# IPMC_Control.net
KiCad netlist of a schematic drawn in Altium Designer
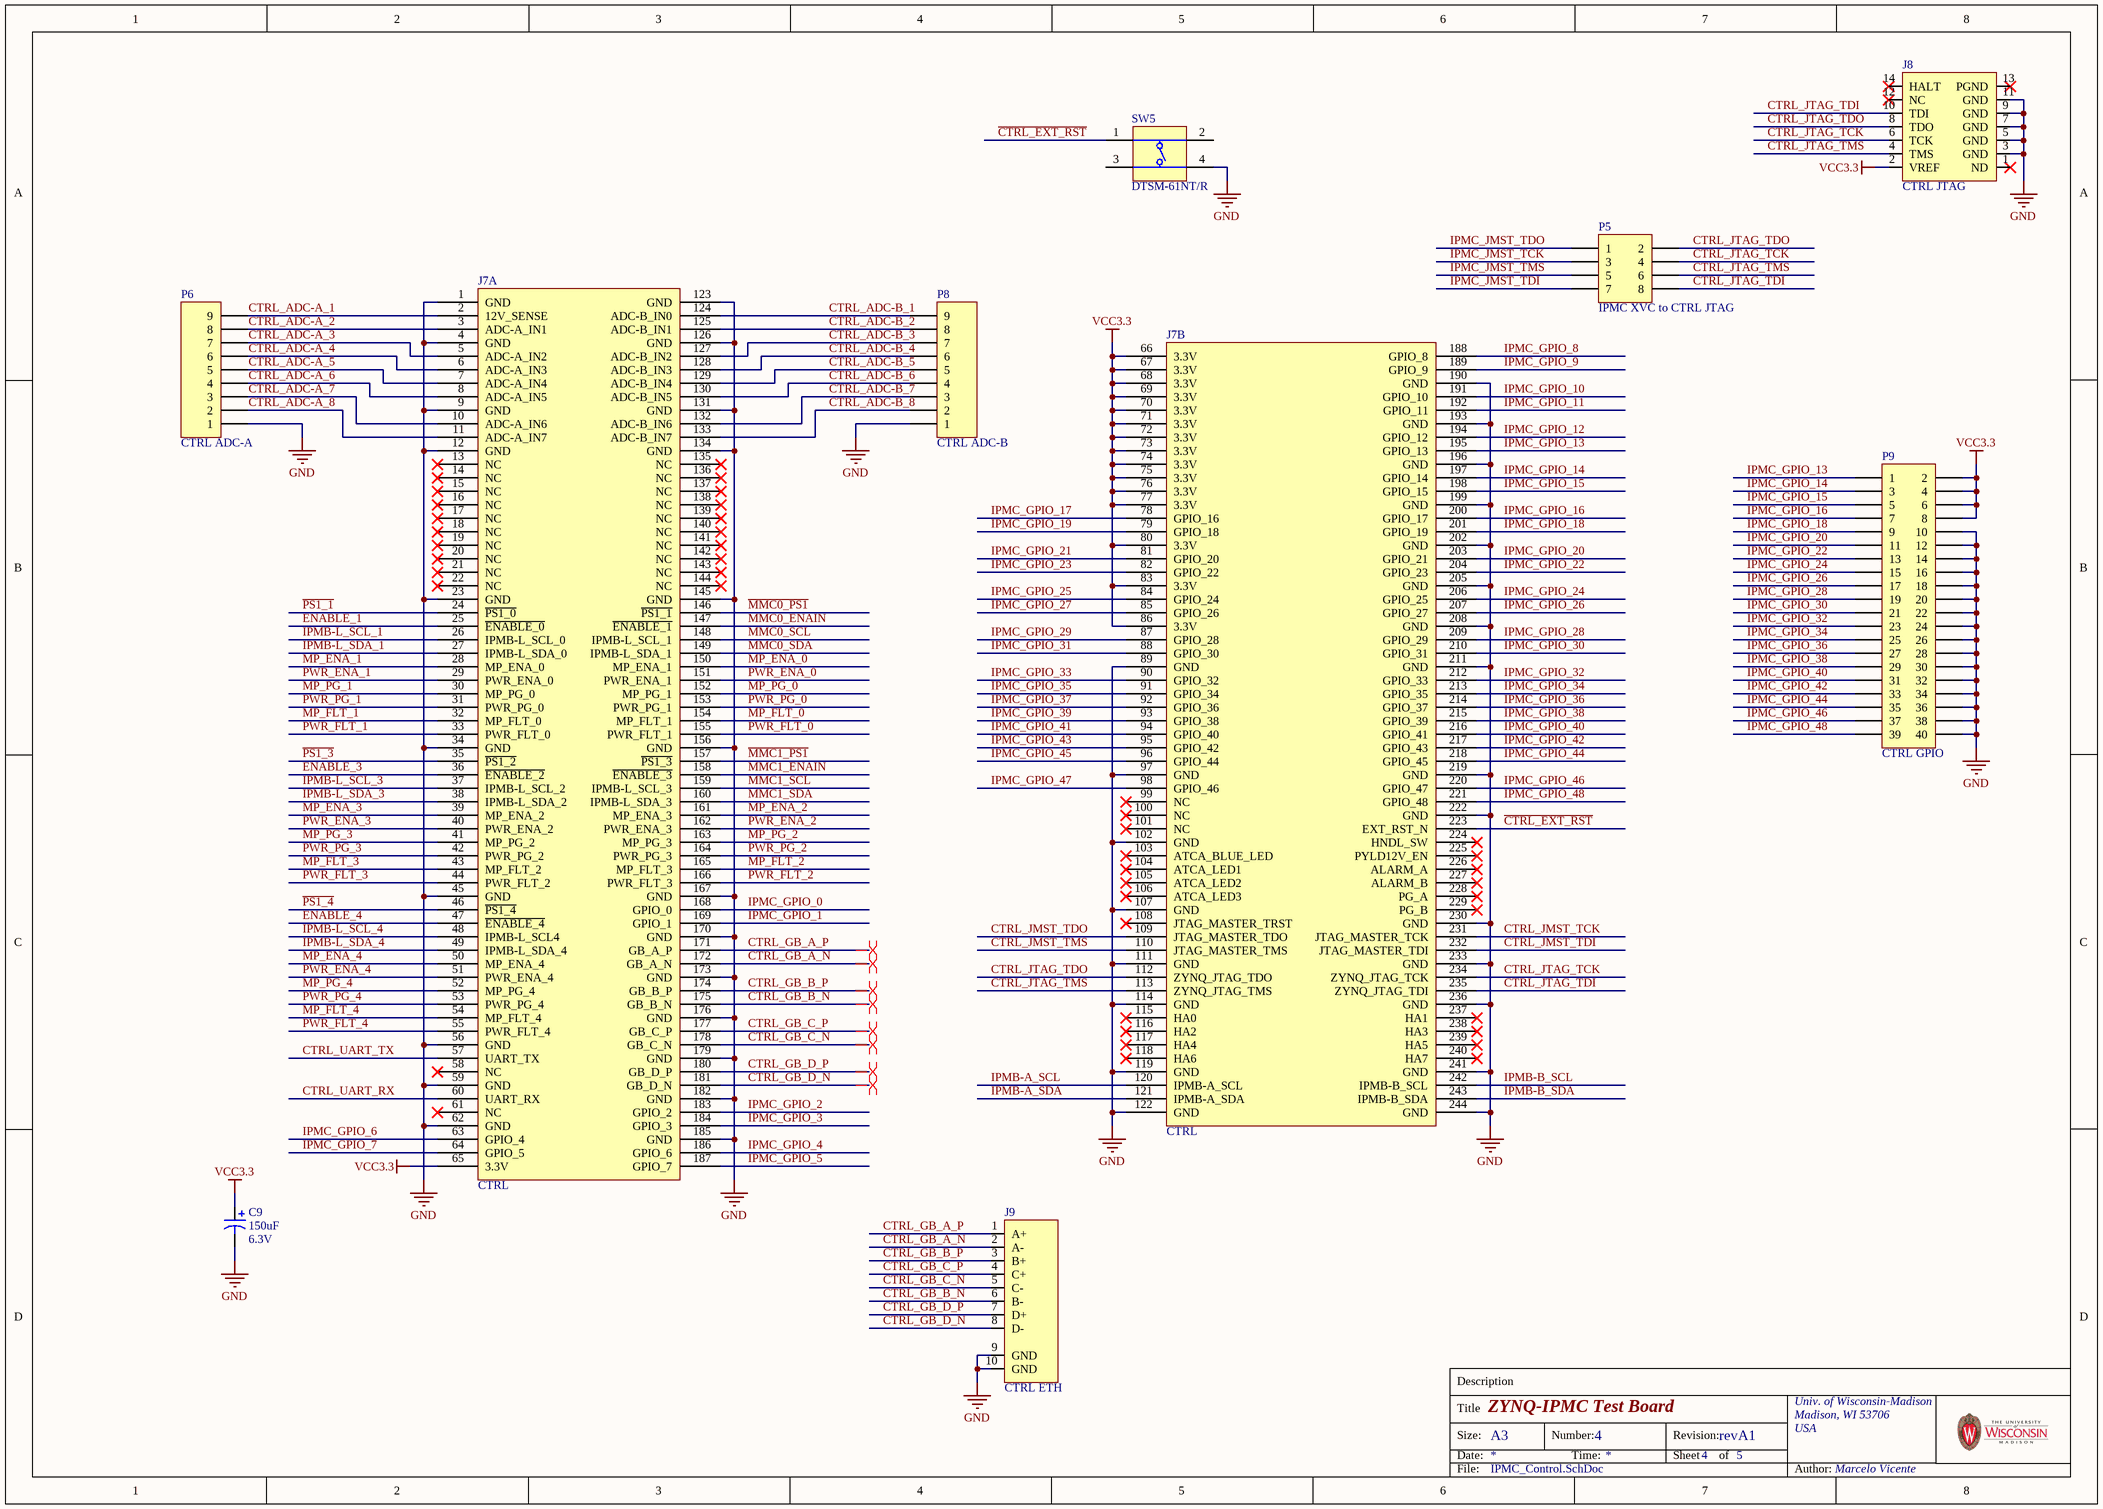
[diagram p0: IPMC_Control.SchDoc]

(export (version "E")
  (design (tool "Eeschema 10.0.6"))
  (components
    (comp (ref "C9")
      (value "150uF")
      (footprint "VISH-293D-7343-31_V")
      (description "Polarized Capacitor (Surface Mount)")
      (fields
        (field (name "RATING") "6.3V")
        (field (name "MFG. PART NO.") "A700X157M006ATE015")
        (field (name "Comment") "?")
      )
      (libsource (lib "Miscellaneous Devices") (part "Cap Pol3"))
    )
    (comp (ref "J7")
      (value "CTRL")
      (footprint "87782-3007")
      (description "Molex 87782-3007")
      (fields (field (name "MFG. PART NO.") "87782-3007"))
      (libsource (lib "CustomSymbols") (part "IPMC"))
    )
    (comp (ref "J8")
      (value "CTRL JTAG")
      (footprint "87832-1420")
      (description "Molex 87832-1420")
      (fields (field (name "MFG. PART NO.") "87832-1420"))
      (libsource (lib "CustomSymbols") (part "Xilinx JTAG Header"))
    )
    (comp (ref "J9")
      (value "CTRL ETH")
      (footprint "43202-8916")
      (description "RJ45 Ethernet Jack")
      (fields (field (name "MFG. PART NO.") "43202-8916"))
      (libsource (lib "CustomSymbols") (part "Ethernet Jack"))
    )
    (comp (ref "P5")
      (value "IPMC XVC to CTRL JTAG")
      (footprint "HEADER2X4")
      (description "Header, 4-Pin, Dual row")
      (fields (field (name "MFG. PART NO.") "?"))
      (libsource (lib "Miscellaneous Connectors") (part "Header 4X2"))
    )
    (comp (ref "P6")
      (value "CTRL ADC-A")
      (footprint "HEADER1X9")
      (description "Header, 9-Pin")
      (fields (field (name "MFG. PART NO.") "?"))
      (libsource (lib "") (part "Header 9_1"))
    )
    (comp (ref "P8")
      (value "CTRL ADC-B")
      (footprint "HEADER1X9")
      (description "Header, 9-Pin")
      (fields (field (name "MFG. PART NO.") "?"))
      (libsource (lib "Miscellaneous Connectors") (part "Header 9"))
    )
    (comp (ref "P9")
      (value "CTRL GPIO")
      (footprint "HEADER2X20")
      (description "Header, 20-Pin, Dual row")
      (fields (field (name "MFG. PART NO.") "?"))
      (libsource (lib "Miscellaneous Connectors") (part "Header 20X2"))
    )
    (comp (ref "SW5")
      (value "DTSM-61NT/R")
      (footprint "DIPT-DTSM-6_V")
      (description "Switch, SPNO Push Button SMD")
      (fields (field (name "MFG. PART NO.") "?"))
      (libsource (lib "Altium Content Vault") (part "DIPT-DTSM-6"))
    )
  )
  (nets
    (net (code "1") (name "/CTRL_ADC-A_1") (class "Default")
      (node (ref "J7") (pin "2") (pinfunction "12V_SENSE_2") (pintype "passive"))
      (node (ref "P6") (pin "9") (pinfunction "9_9") (pintype "passive"))
    )
    (net (code "2") (name "/CTRL_ADC-A_2") (class "Default")
      (node (ref "J7") (pin "3") (pinfunction "ADC-A_IN1_3") (pintype "passive"))
      (node (ref "P6") (pin "8") (pinfunction "8_8") (pintype "passive"))
    )
    (net (code "3") (name "/CTRL_ADC-A_3") (class "Default")
      (node (ref "J7") (pin "5") (pinfunction "ADC-A_IN2_5") (pintype "passive"))
      (node (ref "P6") (pin "7") (pinfunction "7_7") (pintype "passive"))
    )
    (net (code "4") (name "/CTRL_ADC-A_4") (class "Default")
      (node (ref "J7") (pin "6") (pinfunction "ADC-A_IN3_6") (pintype "passive"))
      (node (ref "P6") (pin "6") (pinfunction "6_6") (pintype "passive"))
    )
    (net (code "5") (name "/CTRL_ADC-A_5") (class "Default")
      (node (ref "J7") (pin "7") (pinfunction "ADC-A_IN4_7") (pintype "passive"))
      (node (ref "P6") (pin "5") (pinfunction "5_5") (pintype "passive"))
    )
    (net (code "6") (name "/CTRL_ADC-A_6") (class "Default")
      (node (ref "J7") (pin "8") (pinfunction "ADC-A_IN5_8") (pintype "passive"))
      (node (ref "P6") (pin "4") (pinfunction "4_4") (pintype "passive"))
    )
    (net (code "7") (name "/CTRL_ADC-A_7") (class "Default")
      (node (ref "J7") (pin "10") (pinfunction "ADC-A_IN6_10") (pintype "passive"))
      (node (ref "P6") (pin "3") (pinfunction "3_3") (pintype "passive"))
    )
    (net (code "8") (name "/CTRL_ADC-A_8") (class "Default")
      (node (ref "J7") (pin "11") (pinfunction "ADC-A_IN7_11") (pintype "passive"))
      (node (ref "P6") (pin "2") (pinfunction "2_2") (pintype "passive"))
    )
    (net (code "9") (name "/CTRL_ADC-B_1") (class "Default")
      (node (ref "J7") (pin "124") (pinfunction "ADC-B_IN0_124") (pintype "passive"))
      (node (ref "P8") (pin "9") (pinfunction "9_9") (pintype "passive"))
    )
    (net (code "10") (name "/CTRL_ADC-B_2") (class "Default")
      (node (ref "J7") (pin "125") (pinfunction "ADC-B_IN1_125") (pintype "passive"))
      (node (ref "P8") (pin "8") (pinfunction "8_8") (pintype "passive"))
    )
    (net (code "11") (name "/CTRL_ADC-B_3") (class "Default")
      (node (ref "J7") (pin "127") (pinfunction "ADC-B_IN2_127") (pintype "passive"))
      (node (ref "P8") (pin "7") (pinfunction "7_7") (pintype "passive"))
    )
    (net (code "12") (name "/CTRL_ADC-B_4") (class "Default")
      (node (ref "J7") (pin "128") (pinfunction "ADC-B_IN3_128") (pintype "passive"))
      (node (ref "P8") (pin "6") (pinfunction "6_6") (pintype "passive"))
    )
    (net (code "13") (name "/CTRL_ADC-B_5") (class "Default")
      (node (ref "J7") (pin "129") (pinfunction "ADC-B_IN4_129") (pintype "passive"))
      (node (ref "P8") (pin "5") (pinfunction "5_5") (pintype "passive"))
    )
    (net (code "14") (name "/CTRL_ADC-B_6") (class "Default")
      (node (ref "J7") (pin "130") (pinfunction "ADC-B_IN5_130") (pintype "passive"))
      (node (ref "P8") (pin "4") (pinfunction "4_4") (pintype "passive"))
    )
    (net (code "15") (name "/CTRL_ADC-B_7") (class "Default")
      (node (ref "J7") (pin "132") (pinfunction "ADC-B_IN6_132") (pintype "passive"))
      (node (ref "P8") (pin "3") (pinfunction "3_3") (pintype "passive"))
    )
    (net (code "16") (name "/CTRL_ADC-B_8") (class "Default")
      (node (ref "J7") (pin "133") (pinfunction "ADC-B_IN7_133") (pintype "passive"))
      (node (ref "P8") (pin "2") (pinfunction "2_2") (pintype "passive"))
    )
    (net (code "17") (name "/CTRL_EXT_RST") (class "Default")
      (node (ref "J7") (pin "223") (pinfunction "EXT_RST_N_223") (pintype "passive"))
      (node (ref "SW5") (pin "1") (pinfunction "T1_1") (pintype "passive"))
    )
    (net (code "18") (name "/CTRL_GB_A_N") (class "Default")
      (node (ref "J7") (pin "172") (pinfunction "GB_A_N_172") (pintype "passive"))
      (node (ref "J9") (pin "2") (pinfunction "A-_2") (pintype "passive"))
    )
    (net (code "19") (name "/CTRL_GB_A_P") (class "Default")
      (node (ref "J7") (pin "171") (pinfunction "GB_A_P_171") (pintype "passive"))
      (node (ref "J9") (pin "1") (pinfunction "A+_1") (pintype "passive"))
    )
    (net (code "20") (name "/CTRL_GB_B_N") (class "Default")
      (node (ref "J7") (pin "175") (pinfunction "GB_B_N_175") (pintype "passive"))
      (node (ref "J9") (pin "6") (pinfunction "B-_6") (pintype "passive"))
    )
    (net (code "21") (name "/CTRL_GB_B_P") (class "Default")
      (node (ref "J7") (pin "174") (pinfunction "GB_B_P_174") (pintype "passive"))
      (node (ref "J9") (pin "3") (pinfunction "B+_3") (pintype "passive"))
    )
    (net (code "22") (name "/CTRL_GB_C_N") (class "Default")
      (node (ref "J7") (pin "178") (pinfunction "GB_C_N_178") (pintype "passive"))
      (node (ref "J9") (pin "5") (pinfunction "C-_5") (pintype "passive"))
    )
    (net (code "23") (name "/CTRL_GB_C_P") (class "Default")
      (node (ref "J7") (pin "177") (pinfunction "GB_C_P_177") (pintype "passive"))
      (node (ref "J9") (pin "4") (pinfunction "C+_4") (pintype "passive"))
    )
    (net (code "24") (name "/CTRL_GB_D_N") (class "Default")
      (node (ref "J7") (pin "181") (pinfunction "GB_D_N_181") (pintype "passive"))
      (node (ref "J9") (pin "8") (pinfunction "D-_8") (pintype "passive"))
    )
    (net (code "25") (name "/CTRL_GB_D_P") (class "Default")
      (node (ref "J7") (pin "180") (pinfunction "GB_D_P_180") (pintype "passive"))
      (node (ref "J9") (pin "7") (pinfunction "D+_7") (pintype "passive"))
    )
    (net (code "26") (name "/CTRL_JMST_TCK") (class "Default")
      (node (ref "J7") (pin "231") (pinfunction "JTAG_MASTER_TCK_231") (pintype "passive"))
    )
    (net (code "27") (name "/CTRL_JMST_TDI") (class "Default")
      (node (ref "J7") (pin "232") (pinfunction "JTAG_MASTER_TDI_232") (pintype "passive"))
    )
    (net (code "28") (name "/CTRL_JMST_TDO") (class "Default")
      (node (ref "J7") (pin "109") (pinfunction "JTAG_MASTER_TDO_109") (pintype "passive"))
    )
    (net (code "29") (name "/CTRL_JMST_TMS") (class "Default")
      (node (ref "J7") (pin "110") (pinfunction "JTAG_MASTER_TMS_110") (pintype "passive"))
    )
    (net (code "30") (name "/CTRL_JTAG_TCK") (class "Default")
      (node (ref "J7") (pin "234") (pinfunction "ZYNQ_JTAG_TCK_234") (pintype "passive"))
      (node (ref "J8") (pin "6") (pinfunction "TCK_6") (pintype "passive"))
      (node (ref "P5") (pin "4") (pinfunction "4_4") (pintype "passive"))
    )
    (net (code "31") (name "/CTRL_JTAG_TDI") (class "Default")
      (node (ref "J7") (pin "235") (pinfunction "ZYNQ_JTAG_TDI_235") (pintype "passive"))
      (node (ref "J8") (pin "10") (pinfunction "TDI_10") (pintype "passive"))
      (node (ref "P5") (pin "8") (pinfunction "8_8") (pintype "passive"))
    )
    (net (code "32") (name "/CTRL_JTAG_TDO") (class "Default")
      (node (ref "J7") (pin "112") (pinfunction "ZYNQ_JTAG_TDO_112") (pintype "passive"))
      (node (ref "J8") (pin "8") (pinfunction "TDO_8") (pintype "passive"))
      (node (ref "P5") (pin "2") (pinfunction "2_2") (pintype "passive"))
    )
    (net (code "33") (name "/CTRL_JTAG_TMS") (class "Default")
      (node (ref "J7") (pin "113") (pinfunction "ZYNQ_JTAG_TMS_113") (pintype "passive"))
      (node (ref "J8") (pin "4") (pinfunction "TMS_4") (pintype "passive"))
      (node (ref "P5") (pin "6") (pinfunction "6_6") (pintype "passive"))
    )
    (net (code "34") (name "/CTRL_UART_RX") (class "Default")
      (node (ref "J7") (pin "60") (pinfunction "UART_RX_60") (pintype "passive"))
    )
    (net (code "35") (name "/CTRL_UART_TX") (class "Default")
      (node (ref "J7") (pin "57") (pinfunction "UART_TX_57") (pintype "passive"))
    )
    (net (code "36") (name "/ENABLE_1") (class "Default")
      (node (ref "J7") (pin "25") (pinfunction "ENABLE_0_25") (pintype "passive"))
    )
    (net (code "37") (name "/ENABLE_3") (class "Default")
      (node (ref "J7") (pin "36") (pinfunction "ENABLE_2_36") (pintype "passive"))
    )
    (net (code "38") (name "/ENABLE_4") (class "Default")
      (node (ref "J7") (pin "47") (pinfunction "ENABLE_4_47") (pintype "passive"))
    )
    (net (code "39") (name "/IPMB-A_SCL") (class "Default")
      (node (ref "J7") (pin "120") (pinfunction "IPMB-A_SCL_120") (pintype "passive"))
    )
    (net (code "40") (name "/IPMB-A_SDA") (class "Default")
      (node (ref "J7") (pin "121") (pinfunction "IPMB-A_SDA_121") (pintype "passive"))
    )
    (net (code "41") (name "/IPMB-B_SCL") (class "Default")
      (node (ref "J7") (pin "242") (pinfunction "IPMB-B_SCL_242") (pintype "passive"))
    )
    (net (code "42") (name "/IPMB-B_SDA") (class "Default")
      (node (ref "J7") (pin "243") (pinfunction "IPMB-B_SDA_243") (pintype "passive"))
    )
    (net (code "43") (name "/IPMB-L_SCL_1") (class "Default")
      (node (ref "J7") (pin "26") (pinfunction "IPMB-L_SCL_0_26") (pintype "passive"))
    )
    (net (code "44") (name "/IPMB-L_SCL_3") (class "Default")
      (node (ref "J7") (pin "37") (pinfunction "IPMB-L_SCL_2_37") (pintype "passive"))
    )
    (net (code "45") (name "/IPMB-L_SCL_4") (class "Default")
      (node (ref "J7") (pin "48") (pinfunction "IPMB-L_SCL4_48") (pintype "passive"))
    )
    (net (code "46") (name "/IPMB-L_SDA_1") (class "Default")
      (node (ref "J7") (pin "27") (pinfunction "IPMB-L_SDA_0_27") (pintype "passive"))
    )
    (net (code "47") (name "/IPMB-L_SDA_3") (class "Default")
      (node (ref "J7") (pin "38") (pinfunction "IPMB-L_SDA_2_38") (pintype "passive"))
    )
    (net (code "48") (name "/IPMB-L_SDA_4") (class "Default")
      (node (ref "J7") (pin "49") (pinfunction "IPMB-L_SDA_4_49") (pintype "passive"))
    )
    (net (code "49") (name "/IPMC_GPIO_0") (class "Default")
      (node (ref "J7") (pin "168") (pinfunction "GPIO_0_168") (pintype "passive"))
    )
    (net (code "50") (name "/IPMC_GPIO_1") (class "Default")
      (node (ref "J7") (pin "169") (pinfunction "GPIO_1_169") (pintype "passive"))
    )
    (net (code "51") (name "/IPMC_GPIO_2") (class "Default")
      (node (ref "J7") (pin "183") (pinfunction "GPIO_2_183") (pintype "passive"))
    )
    (net (code "52") (name "/IPMC_GPIO_3") (class "Default")
      (node (ref "J7") (pin "184") (pinfunction "GPIO_3_184") (pintype "passive"))
    )
    (net (code "53") (name "/IPMC_GPIO_4") (class "Default")
      (node (ref "J7") (pin "186") (pinfunction "GPIO_6_186") (pintype "passive"))
    )
    (net (code "54") (name "/IPMC_GPIO_5") (class "Default")
      (node (ref "J7") (pin "187") (pinfunction "GPIO_7_187") (pintype "passive"))
    )
    (net (code "55") (name "/IPMC_GPIO_6") (class "Default")
      (node (ref "J7") (pin "63") (pinfunction "GPIO_4_63") (pintype "passive"))
    )
    (net (code "56") (name "/IPMC_GPIO_7") (class "Default")
      (node (ref "J7") (pin "64") (pinfunction "GPIO_5_64") (pintype "passive"))
    )
    (net (code "57") (name "/IPMC_GPIO_8") (class "Default")
      (node (ref "J7") (pin "188") (pinfunction "GPIO_8_188") (pintype "passive"))
    )
    (net (code "58") (name "/IPMC_GPIO_9") (class "Default")
      (node (ref "J7") (pin "189") (pinfunction "GPIO_9_189") (pintype "passive"))
    )
    (net (code "59") (name "/IPMC_GPIO_10") (class "Default")
      (node (ref "J7") (pin "191") (pinfunction "GPIO_10_191") (pintype "passive"))
    )
    (net (code "60") (name "/IPMC_GPIO_11") (class "Default")
      (node (ref "J7") (pin "192") (pinfunction "GPIO_11_192") (pintype "passive"))
    )
    (net (code "61") (name "/IPMC_GPIO_12") (class "Default")
      (node (ref "J7") (pin "194") (pinfunction "GPIO_12_194") (pintype "passive"))
    )
    (net (code "62") (name "/IPMC_GPIO_13") (class "Default")
      (node (ref "J7") (pin "195") (pinfunction "GPIO_13_195") (pintype "passive"))
      (node (ref "P9") (pin "1") (pinfunction "1_1") (pintype "passive"))
    )
    (net (code "63") (name "/IPMC_GPIO_14") (class "Default")
      (node (ref "J7") (pin "197") (pinfunction "GPIO_14_197") (pintype "passive"))
      (node (ref "P9") (pin "3") (pinfunction "3_3") (pintype "passive"))
    )
    (net (code "64") (name "/IPMC_GPIO_15") (class "Default")
      (node (ref "J7") (pin "198") (pinfunction "GPIO_15_198") (pintype "passive"))
      (node (ref "P9") (pin "5") (pinfunction "5_5") (pintype "passive"))
    )
    (net (code "65") (name "/IPMC_GPIO_16") (class "Default")
      (node (ref "J7") (pin "200") (pinfunction "GPIO_17_200") (pintype "passive"))
      (node (ref "P9") (pin "7") (pinfunction "7_7") (pintype "passive"))
    )
    (net (code "66") (name "/IPMC_GPIO_17") (class "Default")
      (node (ref "J7") (pin "78") (pinfunction "GPIO_16_78") (pintype "passive"))
    )
    (net (code "67") (name "/IPMC_GPIO_18") (class "Default")
      (node (ref "J7") (pin "201") (pinfunction "GPIO_19_201") (pintype "passive"))
      (node (ref "P9") (pin "9") (pinfunction "9_9") (pintype "passive"))
    )
    (net (code "68") (name "/IPMC_GPIO_19") (class "Default")
      (node (ref "J7") (pin "79") (pinfunction "GPIO_18_79") (pintype "passive"))
    )
    (net (code "69") (name "/IPMC_GPIO_20") (class "Default")
      (node (ref "J7") (pin "203") (pinfunction "GPIO_21_203") (pintype "passive"))
      (node (ref "P9") (pin "11") (pinfunction "11_11") (pintype "passive"))
    )
    (net (code "70") (name "/IPMC_GPIO_21") (class "Default")
      (node (ref "J7") (pin "81") (pinfunction "GPIO_20_81") (pintype "passive"))
    )
    (net (code "71") (name "/IPMC_GPIO_22") (class "Default")
      (node (ref "J7") (pin "204") (pinfunction "GPIO_23_204") (pintype "passive"))
      (node (ref "P9") (pin "13") (pinfunction "13_13") (pintype "passive"))
    )
    (net (code "72") (name "/IPMC_GPIO_23") (class "Default")
      (node (ref "J7") (pin "82") (pinfunction "GPIO_22_82") (pintype "passive"))
    )
    (net (code "73") (name "/IPMC_GPIO_24") (class "Default")
      (node (ref "J7") (pin "206") (pinfunction "GPIO_25_206") (pintype "passive"))
      (node (ref "P9") (pin "15") (pinfunction "15_15") (pintype "passive"))
    )
    (net (code "74") (name "/IPMC_GPIO_25") (class "Default")
      (node (ref "J7") (pin "84") (pinfunction "GPIO_24_84") (pintype "passive"))
    )
    (net (code "75") (name "/IPMC_GPIO_26") (class "Default")
      (node (ref "J7") (pin "207") (pinfunction "GPIO_27_207") (pintype "passive"))
      (node (ref "P9") (pin "17") (pinfunction "17_17") (pintype "passive"))
    )
    (net (code "76") (name "/IPMC_GPIO_27") (class "Default")
      (node (ref "J7") (pin "85") (pinfunction "GPIO_26_85") (pintype "passive"))
    )
    (net (code "77") (name "/IPMC_GPIO_28") (class "Default")
      (node (ref "J7") (pin "209") (pinfunction "GPIO_29_209") (pintype "passive"))
      (node (ref "P9") (pin "19") (pinfunction "19_19") (pintype "passive"))
    )
    (net (code "78") (name "/IPMC_GPIO_29") (class "Default")
      (node (ref "J7") (pin "87") (pinfunction "GPIO_28_87") (pintype "passive"))
    )
    (net (code "79") (name "/IPMC_GPIO_30") (class "Default")
      (node (ref "J7") (pin "210") (pinfunction "GPIO_31_210") (pintype "passive"))
      (node (ref "P9") (pin "21") (pinfunction "21_21") (pintype "passive"))
    )
    (net (code "80") (name "/IPMC_GPIO_31") (class "Default")
      (node (ref "J7") (pin "88") (pinfunction "GPIO_30_88") (pintype "passive"))
    )
    (net (code "81") (name "/IPMC_GPIO_32") (class "Default")
      (node (ref "J7") (pin "212") (pinfunction "GPIO_33_212") (pintype "passive"))
      (node (ref "P9") (pin "23") (pinfunction "23_23") (pintype "passive"))
    )
    (net (code "82") (name "/IPMC_GPIO_33") (class "Default")
      (node (ref "J7") (pin "90") (pinfunction "GPIO_32_90") (pintype "passive"))
    )
    (net (code "83") (name "/IPMC_GPIO_34") (class "Default")
      (node (ref "J7") (pin "213") (pinfunction "GPIO_35_213") (pintype "passive"))
      (node (ref "P9") (pin "25") (pinfunction "25_25") (pintype "passive"))
    )
    (net (code "84") (name "/IPMC_GPIO_35") (class "Default")
      (node (ref "J7") (pin "91") (pinfunction "GPIO_34_91") (pintype "passive"))
    )
    (net (code "85") (name "/IPMC_GPIO_36") (class "Default")
      (node (ref "J7") (pin "214") (pinfunction "GPIO_37_214") (pintype "passive"))
      (node (ref "P9") (pin "27") (pinfunction "27_27") (pintype "passive"))
    )
    (net (code "86") (name "/IPMC_GPIO_37") (class "Default")
      (node (ref "J7") (pin "92") (pinfunction "GPIO_36_92") (pintype "passive"))
    )
    (net (code "87") (name "/IPMC_GPIO_38") (class "Default")
      (node (ref "J7") (pin "215") (pinfunction "GPIO_39_215") (pintype "passive"))
      (node (ref "P9") (pin "29") (pinfunction "29_29") (pintype "passive"))
    )
    (net (code "88") (name "/IPMC_GPIO_39") (class "Default")
      (node (ref "J7") (pin "93") (pinfunction "GPIO_38_93") (pintype "passive"))
    )
    (net (code "89") (name "/IPMC_GPIO_40") (class "Default")
      (node (ref "J7") (pin "216") (pinfunction "GPIO_41_216") (pintype "passive"))
      (node (ref "P9") (pin "31") (pinfunction "31_31") (pintype "passive"))
    )
    (net (code "90") (name "/IPMC_GPIO_41") (class "Default")
      (node (ref "J7") (pin "94") (pinfunction "GPIO_40_94") (pintype "passive"))
    )
    (net (code "91") (name "/IPMC_GPIO_42") (class "Default")
      (node (ref "J7") (pin "217") (pinfunction "GPIO_43_217") (pintype "passive"))
      (node (ref "P9") (pin "33") (pinfunction "33_33") (pintype "passive"))
    )
    (net (code "92") (name "/IPMC_GPIO_43") (class "Default")
      (node (ref "J7") (pin "95") (pinfunction "GPIO_42_95") (pintype "passive"))
    )
    (net (code "93") (name "/IPMC_GPIO_44") (class "Default")
      (node (ref "J7") (pin "218") (pinfunction "GPIO_45_218") (pintype "passive"))
      (node (ref "P9") (pin "35") (pinfunction "35_35") (pintype "passive"))
    )
    (net (code "94") (name "/IPMC_GPIO_45") (class "Default")
      (node (ref "J7") (pin "96") (pinfunction "GPIO_44_96") (pintype "passive"))
    )
    (net (code "95") (name "/IPMC_GPIO_46") (class "Default")
      (node (ref "J7") (pin "220") (pinfunction "GPIO_47_220") (pintype "passive"))
      (node (ref "P9") (pin "37") (pinfunction "37_37") (pintype "passive"))
    )
    (net (code "96") (name "/IPMC_GPIO_47") (class "Default")
      (node (ref "J7") (pin "98") (pinfunction "GPIO_46_98") (pintype "passive"))
    )
    (net (code "97") (name "/IPMC_GPIO_48") (class "Default")
      (node (ref "J7") (pin "221") (pinfunction "GPIO_48_221") (pintype "passive"))
      (node (ref "P9") (pin "39") (pinfunction "39_39") (pintype "passive"))
    )
    (net (code "98") (name "/IPMC_JMST_TCK") (class "Default")
      (node (ref "P5") (pin "3") (pinfunction "3_3") (pintype "passive"))
    )
    (net (code "99") (name "/IPMC_JMST_TDI") (class "Default")
      (node (ref "P5") (pin "7") (pinfunction "7_7") (pintype "passive"))
    )
    (net (code "100") (name "/IPMC_JMST_TDO") (class "Default")
      (node (ref "P5") (pin "1") (pinfunction "1_1") (pintype "passive"))
    )
    (net (code "101") (name "/IPMC_JMST_TMS") (class "Default")
      (node (ref "P5") (pin "5") (pinfunction "5_5") (pintype "passive"))
    )
    (net (code "102") (name "/MMC0_ENAIN") (class "Default")
      (node (ref "J7") (pin "147") (pinfunction "ENABLE_1_147") (pintype "passive"))
    )
    (net (code "103") (name "/MMC0_PS1") (class "Default")
      (node (ref "J7") (pin "146") (pinfunction "PS1_1_146") (pintype "passive"))
    )
    (net (code "104") (name "/MMC0_SCL") (class "Default")
      (node (ref "J7") (pin "148") (pinfunction "IPMB-L_SCL_1_148") (pintype "passive"))
    )
    (net (code "105") (name "/MMC0_SDA") (class "Default")
      (node (ref "J7") (pin "149") (pinfunction "IPMB-L_SDA_1_149") (pintype "passive"))
    )
    (net (code "106") (name "/MMC1_ENAIN") (class "Default")
      (node (ref "J7") (pin "158") (pinfunction "ENABLE_3_158") (pintype "passive"))
    )
    (net (code "107") (name "/MMC1_PS1") (class "Default")
      (node (ref "J7") (pin "157") (pinfunction "PS1_3_157") (pintype "passive"))
    )
    (net (code "108") (name "/MMC1_SCL") (class "Default")
      (node (ref "J7") (pin "159") (pinfunction "IPMB-L_SCL_3_159") (pintype "passive"))
    )
    (net (code "109") (name "/MMC1_SDA") (class "Default")
      (node (ref "J7") (pin "160") (pinfunction "IPMB-L_SDA_3_160") (pintype "passive"))
    )
    (net (code "110") (name "/MP_ENA_0") (class "Default")
      (node (ref "J7") (pin "150") (pinfunction "MP_ENA_1_150") (pintype "passive"))
    )
    (net (code "111") (name "/MP_ENA_1") (class "Default")
      (node (ref "J7") (pin "28") (pinfunction "MP_ENA_0_28") (pintype "passive"))
    )
    (net (code "112") (name "/MP_ENA_2") (class "Default")
      (node (ref "J7") (pin "161") (pinfunction "MP_ENA_3_161") (pintype "passive"))
    )
    (net (code "113") (name "/MP_ENA_3") (class "Default")
      (node (ref "J7") (pin "39") (pinfunction "MP_ENA_2_39") (pintype "passive"))
    )
    (net (code "114") (name "/MP_ENA_4") (class "Default")
      (node (ref "J7") (pin "50") (pinfunction "MP_ENA_4_50") (pintype "passive"))
    )
    (net (code "115") (name "/MP_FLT_0") (class "Default")
      (node (ref "J7") (pin "154") (pinfunction "MP_FLT_1_154") (pintype "passive"))
    )
    (net (code "116") (name "/MP_FLT_1") (class "Default")
      (node (ref "J7") (pin "32") (pinfunction "MP_FLT_0_32") (pintype "passive"))
    )
    (net (code "117") (name "/MP_FLT_2") (class "Default")
      (node (ref "J7") (pin "165") (pinfunction "MP_FLT_3_165") (pintype "passive"))
    )
    (net (code "118") (name "/MP_FLT_3") (class "Default")
      (node (ref "J7") (pin "43") (pinfunction "MP_FLT_2_43") (pintype "passive"))
    )
    (net (code "119") (name "/MP_FLT_4") (class "Default")
      (node (ref "J7") (pin "54") (pinfunction "MP_FLT_4_54") (pintype "passive"))
    )
    (net (code "120") (name "/MP_PG_0") (class "Default")
      (node (ref "J7") (pin "152") (pinfunction "MP_PG_1_152") (pintype "passive"))
    )
    (net (code "121") (name "/MP_PG_1") (class "Default")
      (node (ref "J7") (pin "30") (pinfunction "MP_PG_0_30") (pintype "passive"))
    )
    (net (code "122") (name "/MP_PG_2") (class "Default")
      (node (ref "J7") (pin "163") (pinfunction "MP_PG_3_163") (pintype "passive"))
    )
    (net (code "123") (name "/MP_PG_3") (class "Default")
      (node (ref "J7") (pin "41") (pinfunction "MP_PG_2_41") (pintype "passive"))
    )
    (net (code "124") (name "/MP_PG_4") (class "Default")
      (node (ref "J7") (pin "52") (pinfunction "MP_PG_4_52") (pintype "passive"))
    )
    (net (code "125") (name "/PS1_1") (class "Default")
      (node (ref "J7") (pin "24") (pinfunction "PS1_0_24") (pintype "passive"))
    )
    (net (code "126") (name "/PS1_3") (class "Default")
      (node (ref "J7") (pin "35") (pinfunction "PS1_2_35") (pintype "passive"))
    )
    (net (code "127") (name "/PS1_4") (class "Default")
      (node (ref "J7") (pin "46") (pinfunction "PS1_4_46") (pintype "passive"))
    )
    (net (code "128") (name "/PWR_ENA_0") (class "Default")
      (node (ref "J7") (pin "151") (pinfunction "PWR_ENA_1_151") (pintype "passive"))
    )
    (net (code "129") (name "/PWR_ENA_1") (class "Default")
      (node (ref "J7") (pin "29") (pinfunction "PWR_ENA_0_29") (pintype "passive"))
    )
    (net (code "130") (name "/PWR_ENA_2") (class "Default")
      (node (ref "J7") (pin "162") (pinfunction "PWR_ENA_3_162") (pintype "passive"))
    )
    (net (code "131") (name "/PWR_ENA_3") (class "Default")
      (node (ref "J7") (pin "40") (pinfunction "PWR_ENA_2_40") (pintype "passive"))
    )
    (net (code "132") (name "/PWR_ENA_4") (class "Default")
      (node (ref "J7") (pin "51") (pinfunction "PWR_ENA_4_51") (pintype "passive"))
    )
    (net (code "133") (name "/PWR_FLT_0") (class "Default")
      (node (ref "J7") (pin "155") (pinfunction "PWR_FLT_1_155") (pintype "passive"))
    )
    (net (code "134") (name "/PWR_FLT_1") (class "Default")
      (node (ref "J7") (pin "33") (pinfunction "PWR_FLT_0_33") (pintype "passive"))
    )
    (net (code "135") (name "/PWR_FLT_2") (class "Default")
      (node (ref "J7") (pin "166") (pinfunction "PWR_FLT_3_166") (pintype "passive"))
    )
    (net (code "136") (name "/PWR_FLT_3") (class "Default")
      (node (ref "J7") (pin "44") (pinfunction "PWR_FLT_2_44") (pintype "passive"))
    )
    (net (code "137") (name "/PWR_FLT_4") (class "Default")
      (node (ref "J7") (pin "55") (pinfunction "PWR_FLT_4_55") (pintype "passive"))
    )
    (net (code "138") (name "/PWR_PG_0") (class "Default")
      (node (ref "J7") (pin "153") (pinfunction "PWR_PG_1_153") (pintype "passive"))
    )
    (net (code "139") (name "/PWR_PG_1") (class "Default")
      (node (ref "J7") (pin "31") (pinfunction "PWR_PG_0_31") (pintype "passive"))
    )
    (net (code "140") (name "/PWR_PG_2") (class "Default")
      (node (ref "J7") (pin "164") (pinfunction "PWR_PG_3_164") (pintype "passive"))
    )
    (net (code "141") (name "/PWR_PG_3") (class "Default")
      (node (ref "J7") (pin "42") (pinfunction "PWR_PG_2_42") (pintype "passive"))
    )
    (net (code "142") (name "/PWR_PG_4") (class "Default")
      (node (ref "J7") (pin "53") (pinfunction "PWR_PG_4_53") (pintype "passive"))
    )
    (net (code "143") (name "GND") (class "Default")
      (node (ref "C9") (pin "2") (pinfunction "2_2") (pintype "passive"))
      (node (ref "J7") (pin "1") (pinfunction "GND_1") (pintype "passive"))
      (node (ref "J7") (pin "102") (pinfunction "GND_102") (pintype "passive"))
      (node (ref "J7") (pin "107") (pinfunction "GND_107") (pintype "passive"))
      (node (ref "J7") (pin "111") (pinfunction "GND_111") (pintype "passive"))
      (node (ref "J7") (pin "114") (pinfunction "GND_114") (pintype "passive"))
      (node (ref "J7") (pin "119") (pinfunction "GND_119") (pintype "passive"))
      (node (ref "J7") (pin "12") (pinfunction "GND_12") (pintype "passive"))
      (node (ref "J7") (pin "122") (pinfunction "GND_122") (pintype "passive"))
      (node (ref "J7") (pin "123") (pinfunction "GND_123") (pintype "passive"))
      (node (ref "J7") (pin "126") (pinfunction "GND_126") (pintype "passive"))
      (node (ref "J7") (pin "131") (pinfunction "GND_131") (pintype "passive"))
      (node (ref "J7") (pin "134") (pinfunction "GND_134") (pintype "passive"))
      (node (ref "J7") (pin "145") (pinfunction "GND_145") (pintype "passive"))
      (node (ref "J7") (pin "156") (pinfunction "GND_156") (pintype "passive"))
      (node (ref "J7") (pin "167") (pinfunction "GND_167") (pintype "passive"))
      (node (ref "J7") (pin "170") (pinfunction "GND_170") (pintype "passive"))
      (node (ref "J7") (pin "173") (pinfunction "GND_173") (pintype "passive"))
      (node (ref "J7") (pin "176") (pinfunction "GND_176") (pintype "passive"))
      (node (ref "J7") (pin "179") (pinfunction "GND_179") (pintype "passive"))
      (node (ref "J7") (pin "182") (pinfunction "GND_182") (pintype "passive"))
      (node (ref "J7") (pin "185") (pinfunction "GND_185") (pintype "passive"))
      (node (ref "J7") (pin "190") (pinfunction "GND_190") (pintype "passive"))
      (node (ref "J7") (pin "193") (pinfunction "GND_193") (pintype "passive"))
      (node (ref "J7") (pin "196") (pinfunction "GND_196") (pintype "passive"))
      (node (ref "J7") (pin "199") (pinfunction "GND_199") (pintype "passive"))
      (node (ref "J7") (pin "202") (pinfunction "GND_202") (pintype "passive"))
      (node (ref "J7") (pin "205") (pinfunction "GND_205") (pintype "passive"))
      (node (ref "J7") (pin "208") (pinfunction "GND_208") (pintype "passive"))
      (node (ref "J7") (pin "211") (pinfunction "GND_211") (pintype "passive"))
      (node (ref "J7") (pin "219") (pinfunction "GND_219") (pintype "passive"))
      (node (ref "J7") (pin "222") (pinfunction "GND_222") (pintype "passive"))
      (node (ref "J7") (pin "23") (pinfunction "GND_23") (pintype "passive"))
      (node (ref "J7") (pin "230") (pinfunction "GND_230") (pintype "passive"))
      (node (ref "J7") (pin "233") (pinfunction "GND_233") (pintype "passive"))
      (node (ref "J7") (pin "236") (pinfunction "GND_236") (pintype "passive"))
      (node (ref "J7") (pin "241") (pinfunction "GND_241") (pintype "passive"))
      (node (ref "J7") (pin "244") (pinfunction "GND_244") (pintype "passive"))
      (node (ref "J7") (pin "34") (pinfunction "GND_34") (pintype "passive"))
      (node (ref "J7") (pin "4") (pinfunction "GND_4") (pintype "passive"))
      (node (ref "J7") (pin "45") (pinfunction "GND_45") (pintype "passive"))
      (node (ref "J7") (pin "56") (pinfunction "GND_56") (pintype "passive"))
      (node (ref "J7") (pin "59") (pinfunction "GND_59") (pintype "passive"))
      (node (ref "J7") (pin "62") (pinfunction "GND_62") (pintype "passive"))
      (node (ref "J7") (pin "89") (pinfunction "GND_89") (pintype "passive"))
      (node (ref "J7") (pin "9") (pinfunction "GND_9") (pintype "passive"))
      (node (ref "J7") (pin "97") (pinfunction "GND_97") (pintype "passive"))
      (node (ref "J8") (pin "11") (pinfunction "GND_11") (pintype "passive"))
      (node (ref "J8") (pin "3") (pinfunction "GND_3") (pintype "passive"))
      (node (ref "J8") (pin "5") (pinfunction "GND_5") (pintype "passive"))
      (node (ref "J8") (pin "7") (pinfunction "GND_7") (pintype "passive"))
      (node (ref "J8") (pin "9") (pinfunction "GND_9") (pintype "passive"))
      (node (ref "J9") (pin "10") (pinfunction "GND_10") (pintype "passive"))
      (node (ref "J9") (pin "9") (pinfunction "GND_9") (pintype "passive"))
      (node (ref "P6") (pin "1") (pinfunction "1_1") (pintype "passive"))
      (node (ref "P8") (pin "1") (pinfunction "1_1") (pintype "passive"))
      (node (ref "P9") (pin "10") (pinfunction "10_10") (pintype "passive"))
      (node (ref "P9") (pin "12") (pinfunction "12_12") (pintype "passive"))
      (node (ref "P9") (pin "14") (pinfunction "14_14") (pintype "passive"))
      (node (ref "P9") (pin "16") (pinfunction "16_16") (pintype "passive"))
      (node (ref "P9") (pin "18") (pinfunction "18_18") (pintype "passive"))
      (node (ref "P9") (pin "20") (pinfunction "20_20") (pintype "passive"))
      (node (ref "P9") (pin "22") (pinfunction "22_22") (pintype "passive"))
      (node (ref "P9") (pin "24") (pinfunction "24_24") (pintype "passive"))
      (node (ref "P9") (pin "26") (pinfunction "26_26") (pintype "passive"))
      (node (ref "P9") (pin "28") (pinfunction "28_28") (pintype "passive"))
      (node (ref "P9") (pin "30") (pinfunction "30_30") (pintype "passive"))
      (node (ref "P9") (pin "32") (pinfunction "32_32") (pintype "passive"))
      (node (ref "P9") (pin "34") (pinfunction "34_34") (pintype "passive"))
      (node (ref "P9") (pin "36") (pinfunction "36_36") (pintype "passive"))
      (node (ref "P9") (pin "38") (pinfunction "38_38") (pintype "passive"))
      (node (ref "P9") (pin "40") (pinfunction "40_40") (pintype "passive"))
      (node (ref "SW5") (pin "4") (pinfunction "T3_4") (pintype "passive"))
    )
    (net (code "144") (name "VCC3.3") (class "Default")
      (node (ref "C9") (pin "1") (pinfunction "1_1") (pintype "passive"))
      (node (ref "J7") (pin "65") (pinfunction "3.3V_65") (pintype "passive"))
      (node (ref "J7") (pin "66") (pinfunction "3.3V_66") (pintype "passive"))
      (node (ref "J7") (pin "67") (pinfunction "3.3V_67") (pintype "passive"))
      (node (ref "J7") (pin "68") (pinfunction "3.3V_68") (pintype "passive"))
      (node (ref "J7") (pin "69") (pinfunction "3.3V_69") (pintype "passive"))
      (node (ref "J7") (pin "70") (pinfunction "3.3V_70") (pintype "passive"))
      (node (ref "J7") (pin "71") (pinfunction "3.3V_71") (pintype "passive"))
      (node (ref "J7") (pin "72") (pinfunction "3.3V_72") (pintype "passive"))
      (node (ref "J7") (pin "73") (pinfunction "3.3V_73") (pintype "passive"))
      (node (ref "J7") (pin "74") (pinfunction "3.3V_74") (pintype "passive"))
      (node (ref "J7") (pin "75") (pinfunction "3.3V_75") (pintype "passive"))
      (node (ref "J7") (pin "76") (pinfunction "3.3V_76") (pintype "passive"))
      (node (ref "J7") (pin "77") (pinfunction "3.3V_77") (pintype "passive"))
      (node (ref "J7") (pin "80") (pinfunction "3.3V_80") (pintype "passive"))
      (node (ref "J7") (pin "83") (pinfunction "3.3V_83") (pintype "passive"))
      (node (ref "J7") (pin "86") (pinfunction "3.3V_86") (pintype "passive"))
      (node (ref "J8") (pin "2") (pinfunction "VREF_2") (pintype "passive"))
      (node (ref "P9") (pin "2") (pinfunction "2_2") (pintype "passive"))
      (node (ref "P9") (pin "4") (pinfunction "4_4") (pintype "passive"))
      (node (ref "P9") (pin "6") (pinfunction "6_6") (pintype "passive"))
      (node (ref "P9") (pin "8") (pinfunction "8_8") (pintype "passive"))
    )
    (net (code "145") (name "unconnected-(J7A-NC-Pad13)") (class "Default")
      (node (ref "J7") (pin "13") (pinfunction "NC_13") (pintype "passive+no_connect"))
    )
    (net (code "146") (name "unconnected-(J7A-NC-Pad14)") (class "Default")
      (node (ref "J7") (pin "14") (pinfunction "NC_14") (pintype "passive+no_connect"))
    )
    (net (code "147") (name "unconnected-(J7A-NC-Pad15)") (class "Default")
      (node (ref "J7") (pin "15") (pinfunction "NC_15") (pintype "passive+no_connect"))
    )
    (net (code "148") (name "unconnected-(J7A-NC-Pad16)") (class "Default")
      (node (ref "J7") (pin "16") (pinfunction "NC_16") (pintype "passive+no_connect"))
    )
    (net (code "149") (name "unconnected-(J7A-NC-Pad17)") (class "Default")
      (node (ref "J7") (pin "17") (pinfunction "NC_17") (pintype "passive+no_connect"))
    )
    (net (code "150") (name "unconnected-(J7A-NC-Pad18)") (class "Default")
      (node (ref "J7") (pin "18") (pinfunction "NC_18") (pintype "passive+no_connect"))
    )
    (net (code "151") (name "unconnected-(J7A-NC-Pad19)") (class "Default")
      (node (ref "J7") (pin "19") (pinfunction "NC_19") (pintype "passive+no_connect"))
    )
    (net (code "152") (name "unconnected-(J7A-NC-Pad20)") (class "Default")
      (node (ref "J7") (pin "20") (pinfunction "NC_20") (pintype "passive+no_connect"))
    )
    (net (code "153") (name "unconnected-(J7A-NC-Pad21)") (class "Default")
      (node (ref "J7") (pin "21") (pinfunction "NC_21") (pintype "passive+no_connect"))
    )
    (net (code "154") (name "unconnected-(J7A-NC-Pad22)") (class "Default")
      (node (ref "J7") (pin "22") (pinfunction "NC_22") (pintype "passive+no_connect"))
    )
    (net (code "155") (name "unconnected-(J7A-NC-Pad58)") (class "Default")
      (node (ref "J7") (pin "58") (pinfunction "NC_58") (pintype "passive+no_connect"))
    )
    (net (code "156") (name "unconnected-(J7A-NC-Pad61)") (class "Default")
      (node (ref "J7") (pin "61") (pinfunction "NC_61") (pintype "passive+no_connect"))
    )
    (net (code "157") (name "unconnected-(J7A-NC-Pad135)") (class "Default")
      (node (ref "J7") (pin "135") (pinfunction "NC_135") (pintype "passive+no_connect"))
    )
    (net (code "158") (name "unconnected-(J7A-NC-Pad136)") (class "Default")
      (node (ref "J7") (pin "136") (pinfunction "NC_136") (pintype "passive+no_connect"))
    )
    (net (code "159") (name "unconnected-(J7A-NC-Pad137)") (class "Default")
      (node (ref "J7") (pin "137") (pinfunction "NC_137") (pintype "passive+no_connect"))
    )
    (net (code "160") (name "unconnected-(J7A-NC-Pad138)") (class "Default")
      (node (ref "J7") (pin "138") (pinfunction "NC_138") (pintype "passive+no_connect"))
    )
    (net (code "161") (name "unconnected-(J7A-NC-Pad139)") (class "Default")
      (node (ref "J7") (pin "139") (pinfunction "NC_139") (pintype "passive+no_connect"))
    )
    (net (code "162") (name "unconnected-(J7A-NC-Pad140)") (class "Default")
      (node (ref "J7") (pin "140") (pinfunction "NC_140") (pintype "passive+no_connect"))
    )
    (net (code "163") (name "unconnected-(J7A-NC-Pad141)") (class "Default")
      (node (ref "J7") (pin "141") (pinfunction "NC_141") (pintype "passive+no_connect"))
    )
    (net (code "164") (name "unconnected-(J7A-NC-Pad142)") (class "Default")
      (node (ref "J7") (pin "142") (pinfunction "NC_142") (pintype "passive+no_connect"))
    )
    (net (code "165") (name "unconnected-(J7A-NC-Pad143)") (class "Default")
      (node (ref "J7") (pin "143") (pinfunction "NC_143") (pintype "passive+no_connect"))
    )
    (net (code "166") (name "unconnected-(J7A-NC-Pad144)") (class "Default")
      (node (ref "J7") (pin "144") (pinfunction "NC_144") (pintype "passive+no_connect"))
    )
    (net (code "167") (name "unconnected-(J7B-ALARM_A-Pad226)") (class "Default")
      (node (ref "J7") (pin "226") (pinfunction "ALARM_A_226") (pintype "passive+no_connect"))
    )
    (net (code "168") (name "unconnected-(J7B-ALARM_B-Pad227)") (class "Default")
      (node (ref "J7") (pin "227") (pinfunction "ALARM_B_227") (pintype "passive+no_connect"))
    )
    (net (code "169") (name "unconnected-(J7B-ATCA_BLUE_LED-Pad103)") (class "Default")
      (node (ref "J7") (pin "103") (pinfunction "ATCA_BLUE_LED_103") (pintype "passive+no_connect"))
    )
    (net (code "170") (name "unconnected-(J7B-ATCA_LED1-Pad104)") (class "Default")
      (node (ref "J7") (pin "104") (pinfunction "ATCA_LED1_104") (pintype "passive+no_connect"))
    )
    (net (code "171") (name "unconnected-(J7B-ATCA_LED2-Pad105)") (class "Default")
      (node (ref "J7") (pin "105") (pinfunction "ATCA_LED2_105") (pintype "passive+no_connect"))
    )
    (net (code "172") (name "unconnected-(J7B-ATCA_LED3-Pad106)") (class "Default")
      (node (ref "J7") (pin "106") (pinfunction "ATCA_LED3_106") (pintype "passive+no_connect"))
    )
    (net (code "173") (name "unconnected-(J7B-HA0-Pad115)") (class "Default")
      (node (ref "J7") (pin "115") (pinfunction "HA0_115") (pintype "passive+no_connect"))
    )
    (net (code "174") (name "unconnected-(J7B-HA1-Pad237)") (class "Default")
      (node (ref "J7") (pin "237") (pinfunction "HA1_237") (pintype "passive+no_connect"))
    )
    (net (code "175") (name "unconnected-(J7B-HA2-Pad116)") (class "Default")
      (node (ref "J7") (pin "116") (pinfunction "HA2_116") (pintype "passive+no_connect"))
    )
    (net (code "176") (name "unconnected-(J7B-HA3-Pad238)") (class "Default")
      (node (ref "J7") (pin "238") (pinfunction "HA3_238") (pintype "passive+no_connect"))
    )
    (net (code "177") (name "unconnected-(J7B-HA4-Pad117)") (class "Default")
      (node (ref "J7") (pin "117") (pinfunction "HA4_117") (pintype "passive+no_connect"))
    )
    (net (code "178") (name "unconnected-(J7B-HA5-Pad239)") (class "Default")
      (node (ref "J7") (pin "239") (pinfunction "HA5_239") (pintype "passive+no_connect"))
    )
    (net (code "179") (name "unconnected-(J7B-HA6-Pad118)") (class "Default")
      (node (ref "J7") (pin "118") (pinfunction "HA6_118") (pintype "passive+no_connect"))
    )
    (net (code "180") (name "unconnected-(J7B-HA7-Pad240)") (class "Default")
      (node (ref "J7") (pin "240") (pinfunction "HA7_240") (pintype "passive+no_connect"))
    )
    (net (code "181") (name "unconnected-(J7B-HNDL_SW-Pad224)") (class "Default")
      (node (ref "J7") (pin "224") (pinfunction "HNDL_SW_224") (pintype "passive+no_connect"))
    )
    (net (code "182") (name "unconnected-(J7B-JTAG_MASTER_TRST-Pad108)") (class "Default")
      (node (ref "J7") (pin "108") (pinfunction "JTAG_MASTER_TRST_108") (pintype "passive+no_connect"))
    )
    (net (code "183") (name "unconnected-(J7B-NC-Pad99)") (class "Default")
      (node (ref "J7") (pin "99") (pinfunction "NC_99") (pintype "passive+no_connect"))
    )
    (net (code "184") (name "unconnected-(J7B-NC-Pad100)") (class "Default")
      (node (ref "J7") (pin "100") (pinfunction "NC_100") (pintype "passive+no_connect"))
    )
    (net (code "185") (name "unconnected-(J7B-NC-Pad101)") (class "Default")
      (node (ref "J7") (pin "101") (pinfunction "NC_101") (pintype "passive+no_connect"))
    )
    (net (code "186") (name "unconnected-(J7B-PG_A-Pad228)") (class "Default")
      (node (ref "J7") (pin "228") (pinfunction "PG_A_228") (pintype "passive+no_connect"))
    )
    (net (code "187") (name "unconnected-(J7B-PG_B-Pad229)") (class "Default")
      (node (ref "J7") (pin "229") (pinfunction "PG_B_229") (pintype "passive+no_connect"))
    )
    (net (code "188") (name "unconnected-(J7B-PYLD12V_EN-Pad225)") (class "Default")
      (node (ref "J7") (pin "225") (pinfunction "PYLD12V_EN_225") (pintype "passive+no_connect"))
    )
    (net (code "189") (name "unconnected-(J8-HALT-Pad14)") (class "Default")
      (node (ref "J8") (pin "14") (pinfunction "HALT_14") (pintype "passive+no_connect"))
    )
    (net (code "190") (name "unconnected-(J8-NC-Pad12)") (class "Default")
      (node (ref "J8") (pin "12") (pinfunction "NC_12") (pintype "passive+no_connect"))
    )
    (net (code "191") (name "unconnected-(J8-ND-Pad1)") (class "Default")
      (node (ref "J8") (pin "1") (pinfunction "ND_1") (pintype "passive+no_connect"))
    )
    (net (code "192") (name "unconnected-(J8-PGND-Pad13)") (class "Default")
      (node (ref "J8") (pin "13") (pinfunction "PGND_13") (pintype "passive+no_connect"))
    )
    (net (code "193") (name "unconnected-(SW5-T2-Pad2)") (class "Default")
      (node (ref "SW5") (pin "2") (pinfunction "T2_2") (pintype "passive"))
    )
    (net (code "194") (name "unconnected-(SW5-T3-Pad3)") (class "Default")
      (node (ref "SW5") (pin "3") (pinfunction "T3_3") (pintype "passive"))
    )
  )
)
